# schematic.net
KiCad netlist of a schematic drawn in EAGLE
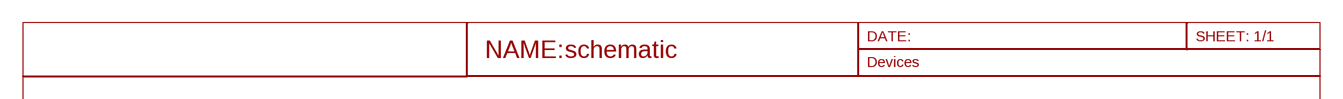
[diagram p0: schematic, sheet 1, part 1 of 2]
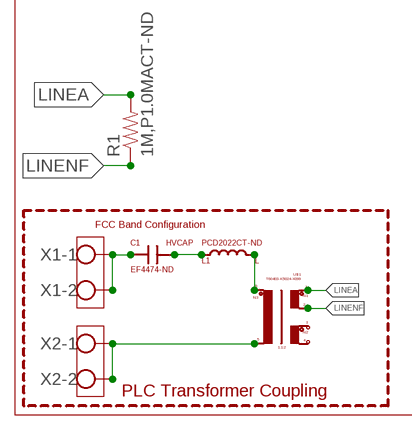
[diagram p1: schematic, sheet 1, part 2 of 2]

(export (version "E")
  (design (tool "Eeschema 10.0.6"))
  (components
    (comp (ref "C1")
      (value "EF4474-ND")
      (footprint "eagle-import:BAGPACK185781715")
      (libsource (lib "eagle-import") (part "EF4474-ND"))
    )
    (comp (ref "L1")
      (value "PCD2022CT-ND")
      (footprint "eagle-import:PCC_INDUCTOR_NONSTANDARD")
      (libsource (lib "eagle-import") (part "PCD2022CT-ND"))
    )
    (comp (ref "R1")
      (value "1M,P1.0MACT-ND")
      (footprint "eagle-import:0805")
      (libsource (lib "eagle-import") (part "RESISTOR0805-RES"))
    )
    (comp (ref "U$1")
      (value "T60403-K5024-X099")
      (footprint "eagle-import:PLCTRNSFTI_PADPOSITION")
      (libsource (lib "eagle-import") (part "T60403-K5024-X099"))
    )
    (comp (ref "X1")
      (value "W237-102")
      (footprint "eagle-import:W237-102")
      (fields (field (name "MPN") "237-102"))
      (libsource (lib "eagle-import") (part "W237-102"))
    )
    (comp (ref "X2")
      (value "W237-102")
      (footprint "eagle-import:W237-102")
      (fields (field (name "MPN") "237-102"))
      (libsource (lib "eagle-import") (part "W237-102"))
    )
  )
  (nets
    (net (code "1") (name "LINEA") (class "Default")
      (node (ref "R1") (pin "2") (pinfunction "2_2") (pintype "passive"))
      (node (ref "U$1") (pin "P1") (pinfunction "P$1_P1") (pintype "bidirectional"))
    )
    (net (code "2") (name "LINENF") (class "Default")
      (node (ref "R1") (pin "1") (pinfunction "1_1") (pintype "passive"))
      (node (ref "U$1") (pin "P2") (pinfunction "P$2_P2") (pintype "bidirectional"))
    )
    (net (code "3") (name "Net-(C1-PadP$2)") (class "Default")
      (node (ref "C1") (pin "P$2") (pinfunction "P$2_P$2") (pintype "bidirectional"))
      (node (ref "L1") (pin "P$1") (pinfunction "P$1_P$1") (pintype "bidirectional"))
    )
    (net (code "4") (name "Net-(U$1-P$5)") (class "Default")
      (node (ref "U$1") (pin "P5") (pinfunction "P$5_P5") (pintype "bidirectional"))
      (node (ref "X2") (pin "1") (pinfunction "KL_1") (pintype "passive"))
      (node (ref "X2") (pin "2") (pinfunction "KL_2") (pintype "passive"))
    )
    (net (code "5") (name "Net-(U$1-P$6)") (class "Default")
      (node (ref "L1") (pin "P$2") (pinfunction "P$2_P$2") (pintype "bidirectional"))
      (node (ref "U$1") (pin "P8") (pinfunction "P$6_P8") (pintype "bidirectional"))
    )
    (net (code "6") (name "Net-(X1A-KL)") (class "Default")
      (node (ref "C1") (pin "P$1") (pinfunction "P$1_P$1") (pintype "bidirectional"))
      (node (ref "X1") (pin "1") (pinfunction "KL_1") (pintype "passive"))
      (node (ref "X1") (pin "2") (pinfunction "KL_2") (pintype "passive"))
    )
    (net (code "7") (name "unconnected-(U$1-P$3-PadP3)") (class "Default")
      (node (ref "U$1") (pin "P3") (pinfunction "P$3_P3") (pintype "bidirectional"))
    )
    (net (code "8") (name "unconnected-(U$1-P$4-PadP4)") (class "Default")
      (node (ref "U$1") (pin "P4") (pinfunction "P$4_P4") (pintype "bidirectional"))
    )
  )
)
